# Planar_HB_1.net
KiCad netlist of a schematic drawn in Altium Designer
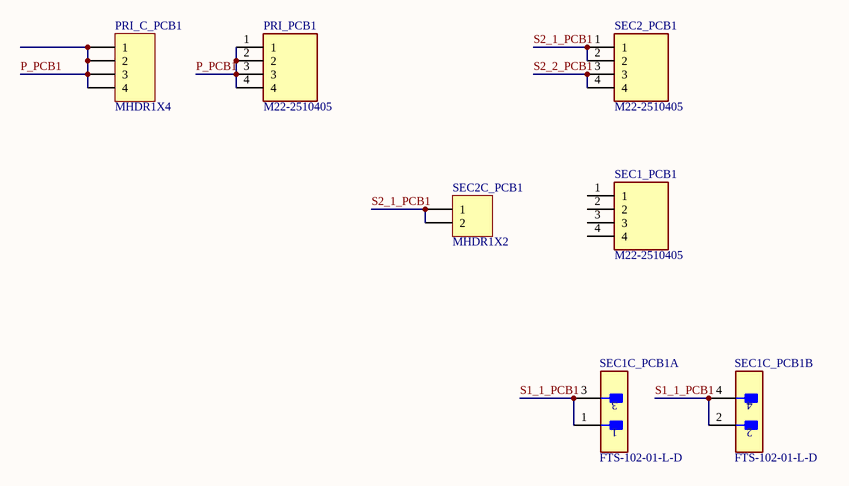
[diagram p0: Planar_HB_1.SchDoc]

(export (version "E")
  (design (tool "Eeschema 10.0.6"))
  (components
    (comp (ref "PRI_C_PCB1")
      (value "MHDR1X4")
      (footprint "MHDR1X4")
      (description "Header, 4-Pin")
      (fields (field (name "PUBLISHER") "Altium Limited"))
      (libsource (lib "Miscellaneous Connectors") (part "MHDR1X4"))
    )
    (comp (ref "PRI_PCB1")
      (value "M22-2510405")
      (footprint "SamacSys:HDRV4W50P0X200_1X4_800X200X525P")
      (description "Connector")
      (fields (field (name "MOUSER PART NUMBER") "855-M22-2510405"))
      (libsource (lib "*") (part "M22-2510405"))
    )
    (comp (ref "SEC1C_PCB1")
      (value "FTS-102-01-L-D")
      (footprint "FP-FTS-102-01-L-D-MFG")
      (description "CONN HEADER VERT 4POS 1.27MM")
      (libsource (lib "Altium Content Vault") (part "1621473add15499e993d6bbd36d0f06"))
    )
    (comp (ref "SEC1_PCB1")
      (value "M22-2510405")
      (footprint "SamacSys:HDRV4W50P0X200_1X4_800X200X525P")
      (description "Connector")
      (fields (field (name "MOUSER PART NUMBER") "855-M22-2510405"))
      (libsource (lib "*") (part "M22-2510405"))
    )
    (comp (ref "SEC2C_PCB1")
      (value "MHDR1X2")
      (footprint "MHDR1X2")
      (description "Header, 2-Pin")
      (fields (field (name "PUBLISHER") "Altium Limited"))
      (libsource (lib "Miscellaneous Connectors") (part "MHDR1X2"))
    )
    (comp (ref "SEC2_PCB1")
      (value "M22-2510405")
      (footprint "SamacSys:HDRV4W50P0X200_1X4_800X200X525P")
      (description "Connector")
      (fields (field (name "MOUSER PART NUMBER") "855-M22-2510405"))
      (libsource (lib "*") (part "M22-2510405"))
    )
  )
  (nets
    (net (code "1") (name "/P_PCB1") (class "Default")
      (node (ref "PRI_C_PCB1") (pin "1") (pinfunction "1_1") (pintype "passive"))
      (node (ref "PRI_C_PCB1") (pin "2") (pinfunction "2_2") (pintype "passive"))
      (node (ref "PRI_C_PCB1") (pin "3") (pinfunction "3_3") (pintype "passive"))
      (node (ref "PRI_C_PCB1") (pin "4") (pinfunction "4_4") (pintype "passive"))
      (node (ref "PRI_PCB1") (pin "1") (pinfunction "1_1") (pintype "passive"))
      (node (ref "PRI_PCB1") (pin "2") (pinfunction "2_2") (pintype "passive"))
      (node (ref "PRI_PCB1") (pin "3") (pinfunction "3_3") (pintype "passive"))
      (node (ref "PRI_PCB1") (pin "4") (pinfunction "4_4") (pintype "passive"))
    )
    (net (code "2") (name "/S1_1_PCB1") (class "Default")
      (node (ref "SEC1C_PCB1") (pin "1") (pinfunction "1_1") (pintype "passive"))
      (node (ref "SEC1C_PCB1") (pin "2") (pinfunction "2_2") (pintype "passive"))
      (node (ref "SEC1C_PCB1") (pin "3") (pinfunction "3_3") (pintype "passive"))
      (node (ref "SEC1C_PCB1") (pin "4") (pinfunction "4_4") (pintype "passive"))
    )
    (net (code "3") (name "/S2_1_PCB1") (class "Default")
      (node (ref "SEC2C_PCB1") (pin "1") (pinfunction "1_1") (pintype "passive"))
      (node (ref "SEC2C_PCB1") (pin "2") (pinfunction "2_2") (pintype "passive"))
      (node (ref "SEC2_PCB1") (pin "1") (pinfunction "1_1") (pintype "passive"))
      (node (ref "SEC2_PCB1") (pin "2") (pinfunction "2_2") (pintype "passive"))
    )
    (net (code "4") (name "/S2_2_PCB1") (class "Default")
      (node (ref "SEC2_PCB1") (pin "3") (pinfunction "3_3") (pintype "passive"))
      (node (ref "SEC2_PCB1") (pin "4") (pinfunction "4_4") (pintype "passive"))
    )
    (net (code "5") (name "unconnected-(SEC1_PCB1-Pad1)") (class "Default")
      (node (ref "SEC1_PCB1") (pin "1") (pinfunction "1_1") (pintype "passive"))
    )
    (net (code "6") (name "unconnected-(SEC1_PCB1-Pad2)") (class "Default")
      (node (ref "SEC1_PCB1") (pin "2") (pinfunction "2_2") (pintype "passive"))
    )
    (net (code "7") (name "unconnected-(SEC1_PCB1-Pad3)") (class "Default")
      (node (ref "SEC1_PCB1") (pin "3") (pinfunction "3_3") (pintype "passive"))
    )
    (net (code "8") (name "unconnected-(SEC1_PCB1-Pad4)") (class "Default")
      (node (ref "SEC1_PCB1") (pin "4") (pinfunction "4_4") (pintype "passive"))
    )
  )
)
